# LEGO_HUB_v2_2026-03-08.net
KiCad netlist of a schematic drawn in EasyEDA Pro
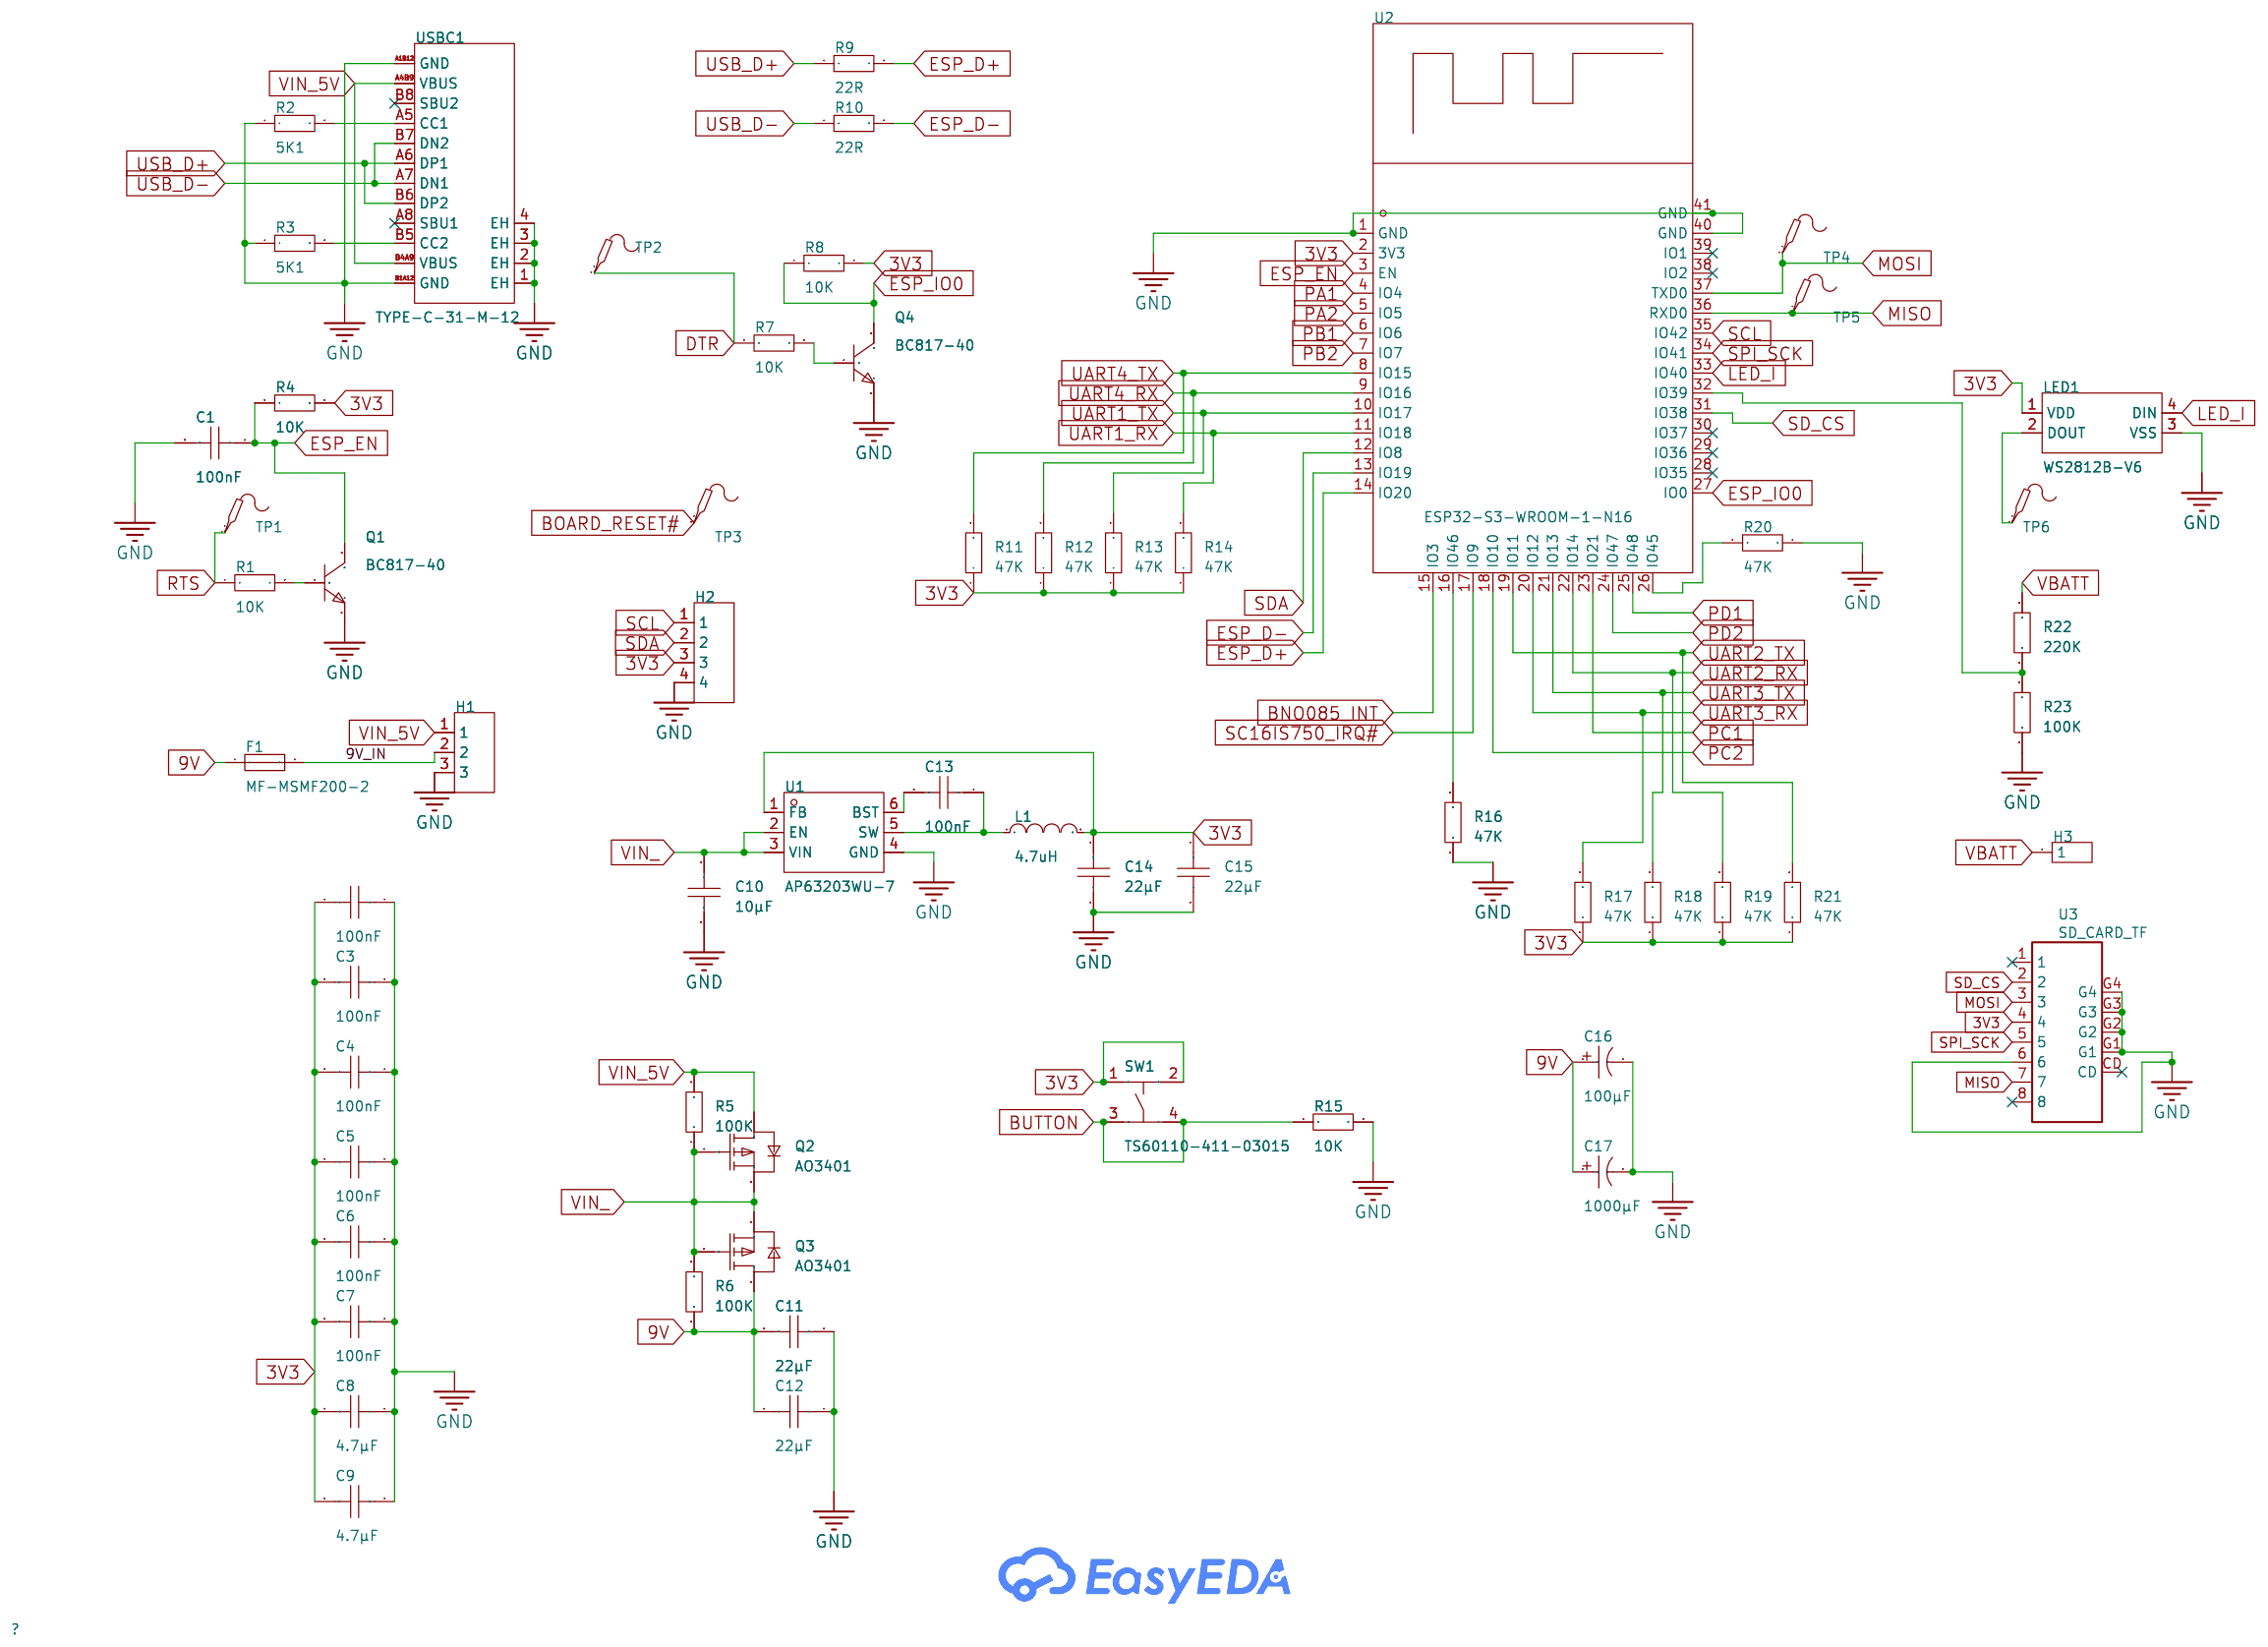
[diagram p0: P1]
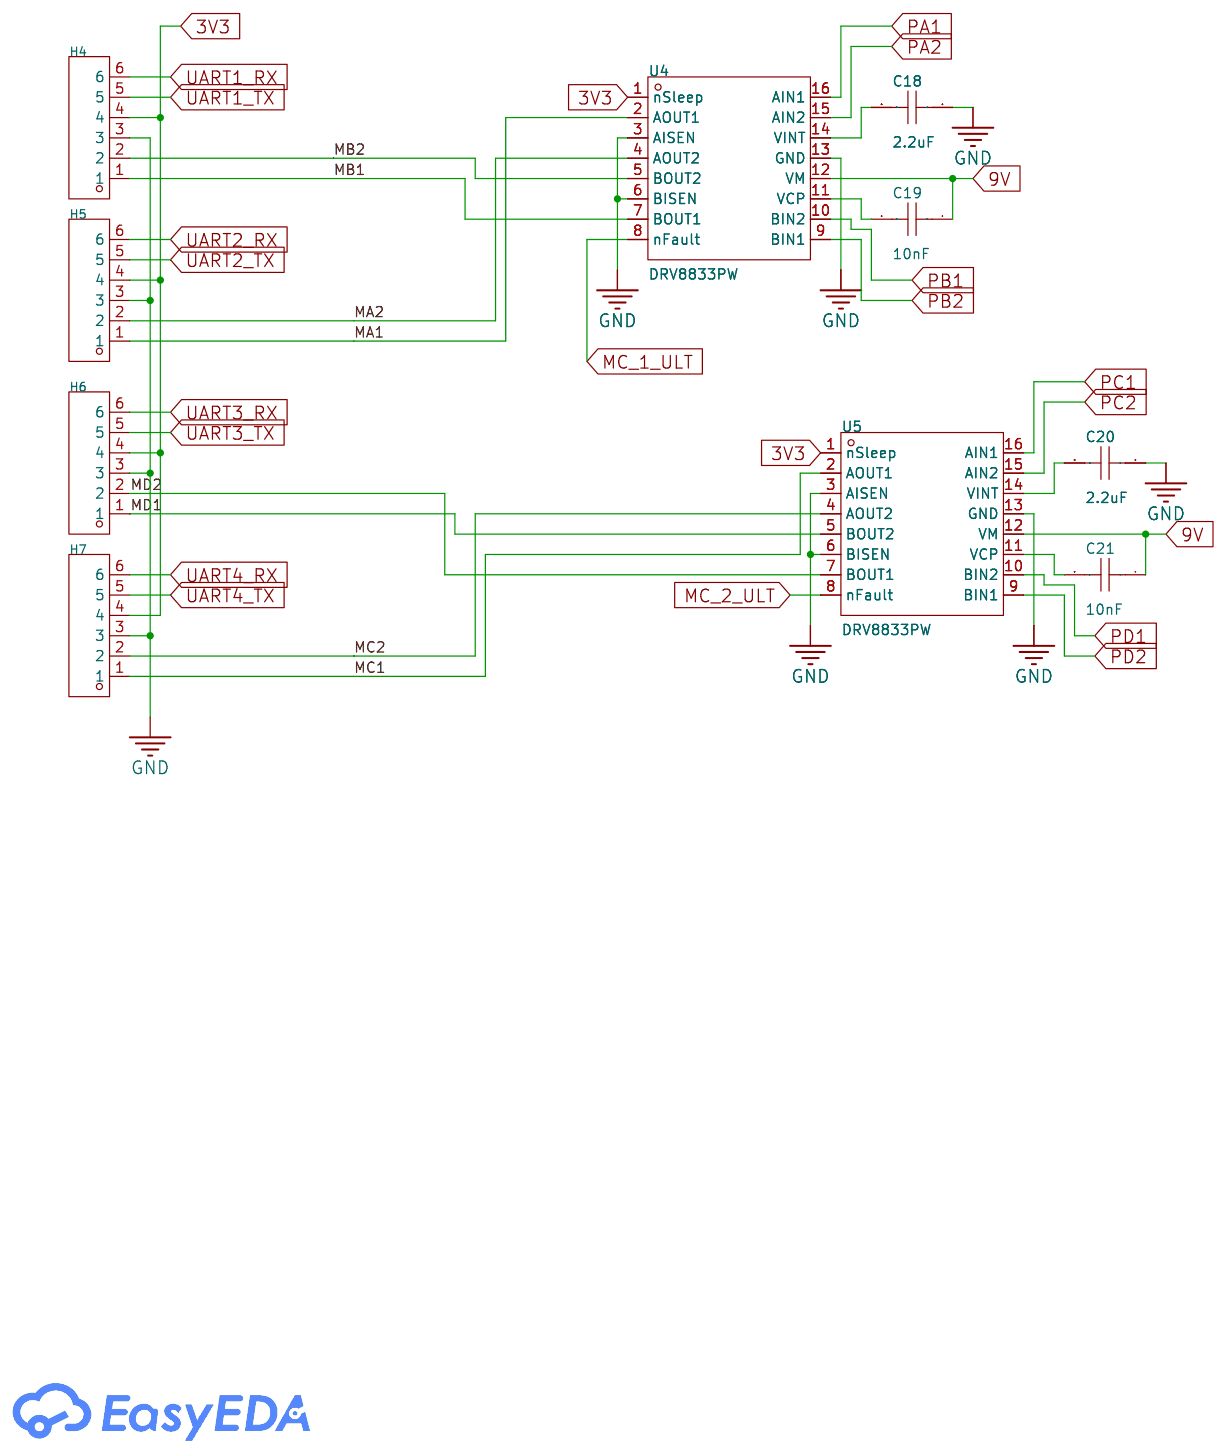
[diagram p1: P2]
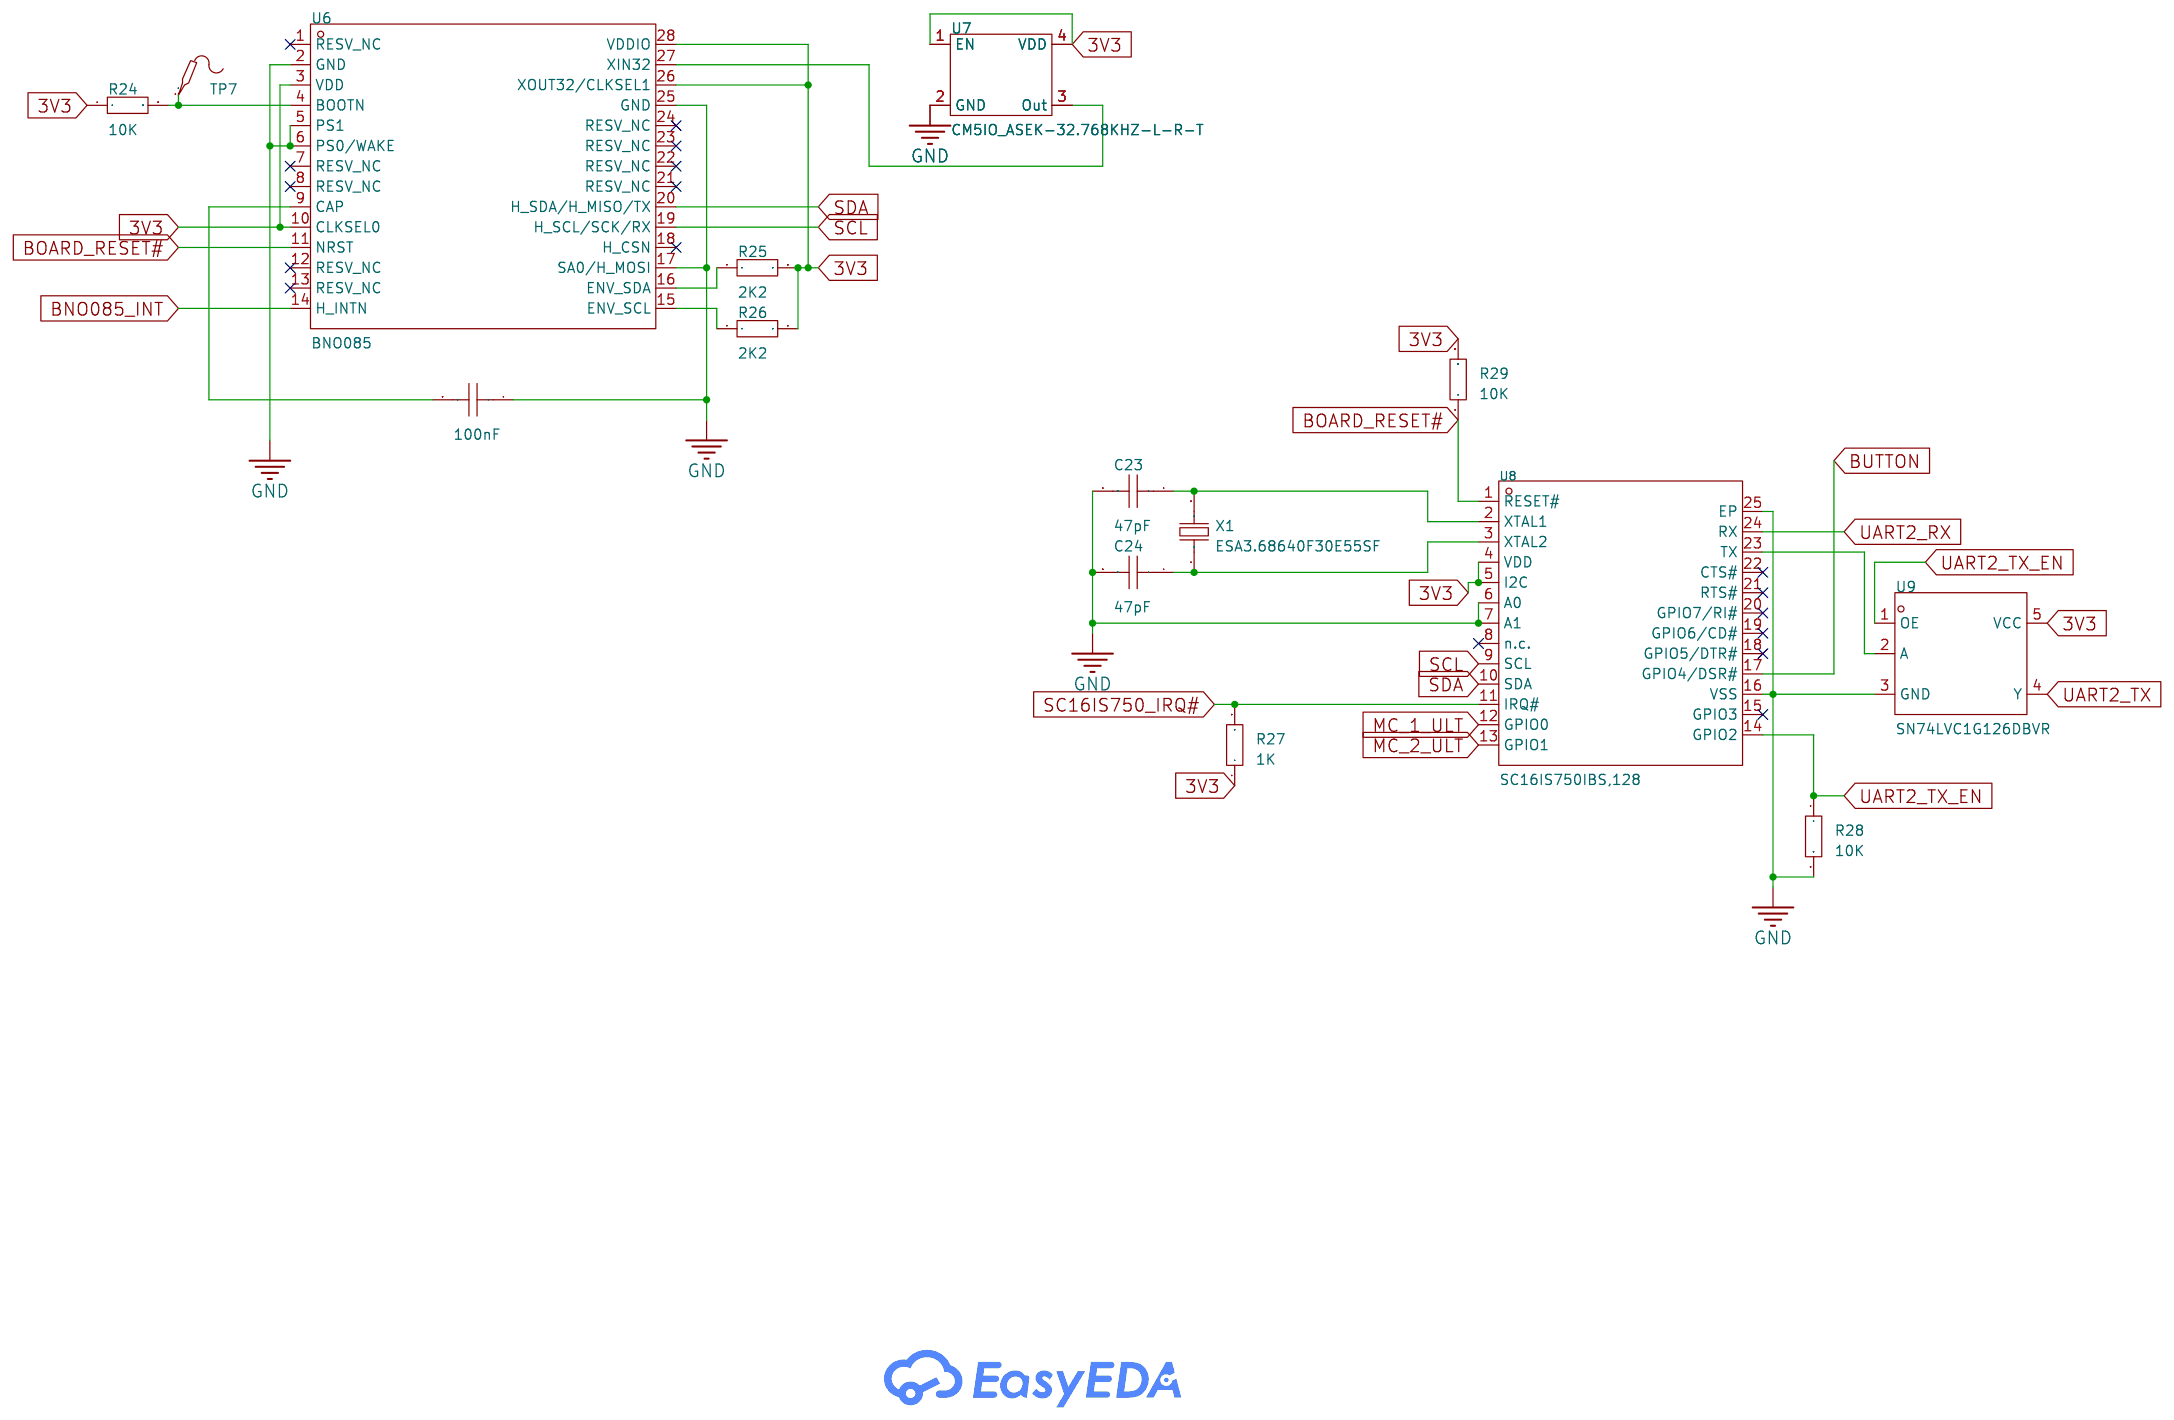
[diagram p2: P3]

(export (version "E")
  (design (tool "Eeschema 10.0.6"))
  (components
    (comp (ref "C1")
      (value "100nF")
      (footprint "easyedapro:C0603")
      (libsource (lib "easyedapro") (part "CAP"))
    )
    (comp (ref "C2")
      (value "100nF")
      (footprint "easyedapro:C0603")
      (libsource (lib "easyedapro") (part "CAP"))
    )
    (comp (ref "C3")
      (value "100nF")
      (footprint "easyedapro:C0603")
      (libsource (lib "easyedapro") (part "CAP"))
    )
    (comp (ref "C4")
      (value "100nF")
      (footprint "easyedapro:C0603")
      (libsource (lib "easyedapro") (part "CAP"))
    )
    (comp (ref "C5")
      (value "100nF")
      (footprint "easyedapro:C0603")
      (libsource (lib "easyedapro") (part "CAP"))
    )
    (comp (ref "C6")
      (value "100nF")
      (footprint "easyedapro:C0603")
      (libsource (lib "easyedapro") (part "CAP"))
    )
    (comp (ref "C7")
      (value "100nF")
      (footprint "easyedapro:C0603")
      (libsource (lib "easyedapro") (part "CAP"))
    )
    (comp (ref "C8")
      (value "4.7μF")
      (footprint "easyedapro:C0603")
      (libsource (lib "easyedapro") (part "CAP"))
    )
    (comp (ref "C9")
      (value "4.7μF")
      (footprint "easyedapro:C0603")
      (libsource (lib "easyedapro") (part "CAP"))
    )
    (comp (ref "C10")
      (value "10μF")
      (footprint "easyedapro:C0603")
      (libsource (lib "easyedapro") (part "CAP"))
    )
    (comp (ref "C11")
      (value "22μF")
      (footprint "easyedapro:C0603")
      (libsource (lib "easyedapro") (part "CAP"))
    )
    (comp (ref "C12")
      (value "22μF")
      (footprint "easyedapro:C0603")
      (libsource (lib "easyedapro") (part "CAP"))
    )
    (comp (ref "C13")
      (value "100nF")
      (footprint "easyedapro:C0603")
      (libsource (lib "easyedapro") (part "CAP"))
    )
    (comp (ref "C14")
      (value "22μF")
      (footprint "easyedapro:C0603")
      (libsource (lib "easyedapro") (part "CAP"))
    )
    (comp (ref "C15")
      (value "22μF")
      (footprint "easyedapro:C0603")
      (libsource (lib "easyedapro") (part "CAP"))
    )
    (comp (ref "C16")
      (value "100μF")
      (footprint "easyedapro:CAP-TH_BD6.3-P2.50-D1.0-FD")
      (fields (field (name "Manufacturer Part") "ERS1HM470E110T") (field (name "Manufacturer") "AISHI(艾华集团)"))
      (libsource (lib "easyedapro") (part "ERS1HM470E110T"))
    )
    (comp (ref "C17")
      (value "1000μF")
      (footprint "easyedapro:CAP-TH_BD10.0-P5.00-D1.0-FD")
      (fields (field (name "Manufacturer Part") "EGD2WM100G16OT") (field (name "Manufacturer") "AISHI(艾华集团)"))
      (libsource (lib "easyedapro") (part "EGD2WM100G16OT"))
    )
    (comp (ref "F1")
      (value "MF-MSMF200-2")
      (footprint "easyedapro:F1812")
      (fields (field (name "Manufacturer") "BOURNS"))
      (libsource (lib "easyedapro") (part "MF-MSMF200-2"))
    )
    (comp (ref "H1")
      (value "~")
      (footprint "easyedapro:HDR-TH_3P-P2.54-V-F")
      (libsource (lib "easyedapro") (part "PM254V-11-03-H85"))
    )
    (comp (ref "H2")
      (value "~")
      (footprint "easyedapro:HDR-TH_4P-P2.54-V-M")
      (libsource (lib "easyedapro") (part "PZ254V-11-04P"))
    )
    (comp (ref "H3")
      (value "~")
      (footprint "easyedapro:HDR-TH_1P-V-M_XKB_X4611WV-01I-C28D40")
      (libsource (lib "easyedapro") (part "HDR_1x1"))
    )
    (comp (ref "L1")
      (value "4.7uH")
      (footprint "easyedapro:IND-SMD_L5.8-W5.2")
      (fields (field (name "Manufacturer Part") "PCD0504MT4R7") (field (name "Manufacturer") "Viking(光颉)"))
      (libsource (lib "easyedapro") (part "PCD0504MT4R7"))
    )
    (comp (ref "LED1")
      (value "WS2812B-V6")
      (footprint "easyedapro:LED-SMD_4P-L5.0-W5.0-TL-A")
      (fields (field (name "Manufacturer") "worldsemi"))
      (libsource (lib "easyedapro") (part "WS2812B-V6"))
    )
    (comp (ref "Q1")
      (value "BC817-40")
      (footprint "easyedapro:SOT-23-3_L2.9-W1.3-P1.90-LS2.4-BR")
      (fields (field (name "Manufacturer") "ElecSuper(静芯)"))
      (libsource (lib "easyedapro") (part "BC817-40_C5249694"))
    )
    (comp (ref "Q2")
      (value "AO3401")
      (footprint "easyedapro:SOT-23-3_L2.9-W1.3-P1.90-LS2.4-BR")
      (fields (field (name "Manufacturer") "YONGYUTAI(永裕泰)"))
      (libsource (lib "easyedapro") (part "AO3401_C6575062"))
    )
    (comp (ref "Q3")
      (value "AO3401")
      (footprint "easyedapro:SOT-23-3_L2.9-W1.3-P1.90-LS2.4-BR")
      (fields (field (name "Manufacturer") "YONGYUTAI(永裕泰)"))
      (libsource (lib "easyedapro") (part "AO3401_C6575062"))
    )
    (comp (ref "Q4")
      (value "BC817-40")
      (footprint "easyedapro:SOT-23-3_L2.9-W1.3-P1.90-LS2.4-BR")
      (fields (field (name "Manufacturer") "ElecSuper(静芯)"))
      (libsource (lib "easyedapro") (part "BC817-40_C5249694"))
    )
    (comp (ref "R1") (value "10K") (footprint "easyedapro:R0201") (libsource (lib "easyedapro") (part "Res")))
    (comp (ref "R2") (value "5K1") (footprint "easyedapro:R0201") (libsource (lib "easyedapro") (part "Res")))
    (comp (ref "R3") (value "5K1") (footprint "easyedapro:R0201") (libsource (lib "easyedapro") (part "Res")))
    (comp (ref "R4") (value "10K") (footprint "easyedapro:R0201") (libsource (lib "easyedapro") (part "Res")))
    (comp (ref "R5")
      (value "100K")
      (footprint "easyedapro:R0201")
      (libsource (lib "easyedapro") (part "Res"))
    )
    (comp (ref "R6")
      (value "100K")
      (footprint "easyedapro:R0201")
      (libsource (lib "easyedapro") (part "Res"))
    )
    (comp (ref "R7") (value "10K") (footprint "easyedapro:R0201") (libsource (lib "easyedapro") (part "Res")))
    (comp (ref "R8") (value "10K") (footprint "easyedapro:R0201") (libsource (lib "easyedapro") (part "Res")))
    (comp (ref "R9") (value "22R") (footprint "easyedapro:R0201") (libsource (lib "easyedapro") (part "Res")))
    (comp (ref "R10")
      (value "22R")
      (footprint "easyedapro:R0201")
      (libsource (lib "easyedapro") (part "Res"))
    )
    (comp (ref "R11")
      (value "47K")
      (footprint "easyedapro:R0201")
      (libsource (lib "easyedapro") (part "Res"))
    )
    (comp (ref "R12")
      (value "47K")
      (footprint "easyedapro:R0201")
      (libsource (lib "easyedapro") (part "Res"))
    )
    (comp (ref "R13")
      (value "47K")
      (footprint "easyedapro:R0201")
      (libsource (lib "easyedapro") (part "Res"))
    )
    (comp (ref "R14")
      (value "47K")
      (footprint "easyedapro:R0201")
      (libsource (lib "easyedapro") (part "Res"))
    )
    (comp (ref "R15")
      (value "10K")
      (footprint "easyedapro:R0201")
      (libsource (lib "easyedapro") (part "Res"))
    )
    (comp (ref "R16")
      (value "47K")
      (footprint "easyedapro:R0201")
      (libsource (lib "easyedapro") (part "Res"))
    )
    (comp (ref "R17")
      (value "47K")
      (footprint "easyedapro:R0201")
      (libsource (lib "easyedapro") (part "Res"))
    )
    (comp (ref "R18")
      (value "47K")
      (footprint "easyedapro:R0201")
      (libsource (lib "easyedapro") (part "Res"))
    )
    (comp (ref "R19")
      (value "47K")
      (footprint "easyedapro:R0201")
      (libsource (lib "easyedapro") (part "Res"))
    )
    (comp (ref "R20")
      (value "47K")
      (footprint "easyedapro:R0201")
      (libsource (lib "easyedapro") (part "Res"))
    )
    (comp (ref "R21")
      (value "47K")
      (footprint "easyedapro:R0201")
      (libsource (lib "easyedapro") (part "Res"))
    )
    (comp (ref "R22")
      (value "220K")
      (footprint "easyedapro:R0201")
      (libsource (lib "easyedapro") (part "Res"))
    )
    (comp (ref "R23")
      (value "100K")
      (footprint "easyedapro:R0201")
      (libsource (lib "easyedapro") (part "Res"))
    )
    (comp (ref "SW1")
      (value "TS60110-411-03015")
      (footprint "easyedapro:SW-SMD_4P-L5.2-W5.2-P3.70-LS6.4-BL")
      (fields (field (name "Manufacturer") "HMTCONN(华明通)"))
      (libsource (lib "easyedapro") (part "TS60110-411-03015"))
    )
    (comp (ref "TP1")
      (value "~")
      (footprint "easyedapro:Test-Point-0.5mm")
      (description "Test Point 测试点")
      (libsource (lib "easyedapro") (part "Test-Point"))
    )
    (comp (ref "TP2")
      (value "~")
      (footprint "easyedapro:Test-Point-0.5mm")
      (description "Test Point 测试点")
      (libsource (lib "easyedapro") (part "Test-Point"))
    )
    (comp (ref "TP3")
      (value "~")
      (footprint "easyedapro:Test-Point-0.5mm")
      (description "Test Point 测试点")
      (libsource (lib "easyedapro") (part "Test-Point"))
    )
    (comp (ref "TP4")
      (value "~")
      (footprint "easyedapro:Test-Point-0.5mm")
      (description "Test Point 测试点")
      (libsource (lib "easyedapro") (part "Test-Point"))
    )
    (comp (ref "TP5")
      (value "~")
      (footprint "easyedapro:Test-Point-0.5mm")
      (description "Test Point 测试点")
      (libsource (lib "easyedapro") (part "Test-Point"))
    )
    (comp (ref "TP6")
      (value "~")
      (footprint "easyedapro:Test-Point-0.5mm")
      (description "Test Point 测试点")
      (libsource (lib "easyedapro") (part "Test-Point"))
    )
    (comp (ref "U1")
      (value "AP63203WU-7")
      (footprint "easyedapro:TSOT-26_L2.9-W1.6-P0.95-LS2.8-BL")
      (fields (field (name "Manufacturer") "DIODES(美台)"))
      (libsource (lib "easyedapro") (part "AP63203WU-7"))
    )
    (comp (ref "U2")
      (value "ESP32-S3-WROOM-1-N16")
      (footprint "easyedapro:WIRELM-SMD_ESP32-S3-WROOM-1")
      (fields (field (name "Manufacturer") "ESPRESSIF(乐鑫)"))
      (libsource (lib "easyedapro") (part "ESP32-S3-WROOM-1(N16)"))
    )
    (comp (ref "U3")
      (value "SD_CARD_TF")
      (footprint "easyedapro:MICRO-USB-SMD_MICRO-SD")
      (fields (field (name "Manufacturer Part") "SD_Card_TF") (field (name "Contributor") "lcsc"))
      (libsource (lib "easyedapro") (part "SD_CARD_TF"))
    )
    (comp (ref "USBC1")
      (value "TYPE-C-31-M-12")
      (footprint "easyedapro:USB-C_SMD-TYPE-C-31-M-12_1")
      (fields (field (name "Manufacturer") "韩国韩荣"))
      (libsource (lib "easyedapro") (part "TYPE-C-31-M-12"))
    )
    (comp (ref "C18")
      (value "2.2uF")
      (footprint "easyedapro:C0603")
      (libsource (lib "easyedapro") (part "CAP"))
    )
    (comp (ref "C19")
      (value "10nF")
      (footprint "easyedapro:C0603")
      (libsource (lib "easyedapro") (part "CAP"))
    )
    (comp (ref "C20")
      (value "2.2uF")
      (footprint "easyedapro:C0603")
      (libsource (lib "easyedapro") (part "CAP"))
    )
    (comp (ref "C21")
      (value "10nF")
      (footprint "easyedapro:C0603")
      (libsource (lib "easyedapro") (part "CAP"))
    )
    (comp (ref "H4")
      (value "~")
      (footprint "easyedapro:HDR-TH_6P-P2.54-V-F")
      (libsource (lib "easyedapro") (part "Header-Female-2.54_1x6"))
    )
    (comp (ref "H5")
      (value "~")
      (footprint "easyedapro:HDR-TH_6P-P2.54-V-F")
      (libsource (lib "easyedapro") (part "Header-Female-2.54_1x6"))
    )
    (comp (ref "H6")
      (value "~")
      (footprint "easyedapro:HDR-TH_6P-P2.54-V-F")
      (libsource (lib "easyedapro") (part "Header-Female-2.54_1x6"))
    )
    (comp (ref "H7")
      (value "~")
      (footprint "easyedapro:HDR-TH_6P-P2.54-V-F")
      (libsource (lib "easyedapro") (part "Header-Female-2.54_1x6"))
    )
    (comp (ref "U4")
      (value "DRV8833PW")
      (footprint "easyedapro:TSSOP-16_L5.0-W4.4-P0.65-LS6.4-BL")
      (fields (field (name "Manufacturer") "TI(德州仪器)"))
      (libsource (lib "easyedapro") (part "DRV8833PW_C3681295"))
    )
    (comp (ref "U5")
      (value "DRV8833PW")
      (footprint "easyedapro:TSSOP-16_L5.0-W4.4-P0.65-LS6.4-BL")
      (fields (field (name "Manufacturer") "TI(德州仪器)"))
      (libsource (lib "easyedapro") (part "DRV8833PW_C3681295"))
    )
    (comp (ref "C22")
      (value "100nF")
      (footprint "easyedapro:C0603")
      (libsource (lib "easyedapro") (part "CAP"))
    )
    (comp (ref "C23")
      (value "47pF")
      (footprint "easyedapro:C0603")
      (libsource (lib "easyedapro") (part "CAP"))
    )
    (comp (ref "C24")
      (value "47pF")
      (footprint "easyedapro:C0603")
      (libsource (lib "easyedapro") (part "CAP"))
    )
    (comp (ref "R24")
      (value "10K")
      (footprint "easyedapro:R0201")
      (libsource (lib "easyedapro") (part "Res"))
    )
    (comp (ref "R25")
      (value "2K2")
      (footprint "easyedapro:R0201")
      (libsource (lib "easyedapro") (part "Res"))
    )
    (comp (ref "R26")
      (value "2K2")
      (footprint "easyedapro:R0201")
      (libsource (lib "easyedapro") (part "Res"))
    )
    (comp (ref "R27") (value "1K") (footprint "easyedapro:R0201") (libsource (lib "easyedapro") (part "Res")))
    (comp (ref "R28")
      (value "10K")
      (footprint "easyedapro:R0201")
      (libsource (lib "easyedapro") (part "Res"))
    )
    (comp (ref "R29")
      (value "10K")
      (footprint "easyedapro:R0201")
      (libsource (lib "easyedapro") (part "Res"))
    )
    (comp (ref "TP7")
      (value "~")
      (footprint "easyedapro:Test-Point-0.5mm")
      (description "Test Point 测试点")
      (libsource (lib "easyedapro") (part "Test-Point"))
    )
    (comp (ref "U6")
      (value "BNO085")
      (footprint "easyedapro:LGA-28_L5.2-W3.8-P0.50-BL")
      (fields (field (name "Manufacturer") "CEVA"))
      (libsource (lib "easyedapro") (part "BNO085_C5189642"))
    )
    (comp (ref "U7")
      (value "ASEK-32.768KHZ-L-R-T")
      (footprint "easyedapro:Crystal:Crystal_SMD_3225-4Pin_3.2x2.5mm")
      (libsource (lib "easyedapro") (part "CM5IO_ASEK-32.768KHZ-L-R-T"))
    )
    (comp (ref "U8")
      (value "SC16IS750IBS,128")
      (footprint "easyedapro:HVQFN-24_L4.0-W4.0-P0.50-BL-EP2.6")
      (fields (field (name "Manufacturer") "NXP(恩智浦)"))
      (libsource (lib "easyedapro") (part "SC16IS750IBS,128"))
    )
    (comp (ref "U9")
      (value "SN74LVC1G126DBVR")
      (footprint "easyedapro:SOT-23-5_L3.0-W1.7-P0.95-LS2.8-BR")
      (fields (field (name "Manufacturer") "TI"))
      (libsource (lib "easyedapro") (part "SN74LVC1G126DBVR"))
    )
    (comp (ref "X1")
      (value "ESA3.68640F30E55SF")
      (footprint "easyedapro:CRYSTAL-SMD_L11.4-W4.7-LS12.7")
      (libsource (lib "easyedapro") (part "ESA3.68640F30E55SF"))
    )
  )
  (nets
    (net (code "1") (name "3V3") (class "Default")
      (node (ref "C14") (pin "1") (pinfunction "1_1") (pintype "input"))
      (node (ref "C15") (pin "1") (pinfunction "1_1") (pintype "input"))
      (node (ref "C2") (pin "2") (pinfunction "2_2") (pintype "input"))
      (node (ref "C3") (pin "2") (pinfunction "2_2") (pintype "input"))
      (node (ref "C4") (pin "2") (pinfunction "2_2") (pintype "input"))
      (node (ref "C5") (pin "2") (pinfunction "2_2") (pintype "input"))
      (node (ref "C6") (pin "2") (pinfunction "2_2") (pintype "input"))
      (node (ref "C7") (pin "2") (pinfunction "2_2") (pintype "input"))
      (node (ref "C8") (pin "2") (pinfunction "2_2") (pintype "input"))
      (node (ref "C9") (pin "2") (pinfunction "2_2") (pintype "input"))
      (node (ref "H2") (pin "3") (pinfunction "3_3") (pintype "unspecified"))
      (node (ref "H4") (pin "4") (pinfunction "4_4") (pintype "input"))
      (node (ref "H5") (pin "4") (pinfunction "4_4") (pintype "input"))
      (node (ref "H6") (pin "4") (pinfunction "4_4") (pintype "input"))
      (node (ref "H7") (pin "4") (pinfunction "4_4") (pintype "input"))
      (node (ref "L1") (pin "2") (pinfunction "2_2") (pintype "unspecified"))
      (node (ref "LED1") (pin "1") (pinfunction "VDD_1") (pintype "unspecified"))
      (node (ref "R11") (pin "1") (pinfunction "1_1") (pintype "input"))
      (node (ref "R12") (pin "1") (pinfunction "1_1") (pintype "input"))
      (node (ref "R13") (pin "1") (pinfunction "1_1") (pintype "input"))
      (node (ref "R14") (pin "1") (pinfunction "1_1") (pintype "input"))
      (node (ref "R17") (pin "1") (pinfunction "1_1") (pintype "input"))
      (node (ref "R18") (pin "1") (pinfunction "1_1") (pintype "input"))
      (node (ref "R19") (pin "1") (pinfunction "1_1") (pintype "input"))
      (node (ref "R21") (pin "1") (pinfunction "1_1") (pintype "input"))
      (node (ref "R24") (pin "1") (pinfunction "1_1") (pintype "input"))
      (node (ref "R25") (pin "2") (pinfunction "2_2") (pintype "input"))
      (node (ref "R26") (pin "2") (pinfunction "2_2") (pintype "input"))
      (node (ref "R27") (pin "1") (pinfunction "1_1") (pintype "input"))
      (node (ref "R29") (pin "2") (pinfunction "2_2") (pintype "input"))
      (node (ref "R4") (pin "2") (pinfunction "2_2") (pintype "input"))
      (node (ref "R8") (pin "2") (pinfunction "2_2") (pintype "input"))
      (node (ref "SW1") (pin "1") (pinfunction "1_1") (pintype "unspecified"))
      (node (ref "SW1") (pin "2") (pinfunction "2_2") (pintype "unspecified"))
      (node (ref "U1") (pin "1") (pinfunction "FB_1") (pintype "unspecified"))
      (node (ref "U2") (pin "2") (pinfunction "3V3_2") (pintype "unspecified"))
      (node (ref "U3") (pin "4") (pinfunction "4_4") (pintype "unspecified"))
      (node (ref "U4") (pin "1") (pinfunction "nSleep_1") (pintype "unspecified"))
      (node (ref "U5") (pin "1") (pinfunction "nSleep_1") (pintype "unspecified"))
      (node (ref "U6") (pin "10") (pinfunction "CLKSEL0_10") (pintype "unspecified"))
      (node (ref "U6") (pin "26") (pinfunction "XOUT32/CLKSEL1_26") (pintype "unspecified"))
      (node (ref "U6") (pin "28") (pinfunction "VDDIO_28") (pintype "unspecified"))
      (node (ref "U6") (pin "3") (pinfunction "VDD_3") (pintype "unspecified"))
      (node (ref "U7") (pin "1") (pinfunction "EN_1") (pintype "input"))
      (node (ref "U7") (pin "4") (pinfunction "VDD_4") (pintype "unspecified"))
      (node (ref "U8") (pin "4") (pinfunction "VDD_4") (pintype "input"))
      (node (ref "U8") (pin "5") (pinfunction "I2C_5") (pintype "input"))
      (node (ref "U9") (pin "5") (pinfunction "VCC_5") (pintype "unspecified"))
    )
    (net (code "2") (name "9V") (class "Default")
      (node (ref "C11") (pin "2") (pinfunction "2_2") (pintype "input"))
      (node (ref "C12") (pin "2") (pinfunction "2_2") (pintype "input"))
      (node (ref "C16") (pin "1") (pinfunction "1_1") (pintype "input"))
      (node (ref "C17") (pin "1") (pinfunction "1_1") (pintype "input"))
      (node (ref "C19") (pin "1") (pinfunction "1_1") (pintype "input"))
      (node (ref "C21") (pin "1") (pinfunction "1_1") (pintype "input"))
      (node (ref "F1") (pin "1") (pinfunction "1_1") (pintype "unspecified"))
      (node (ref "Q3") (pin "3") (pinfunction "D_3") (pintype "unspecified"))
      (node (ref "R6") (pin "1") (pinfunction "1_1") (pintype "input"))
      (node (ref "U4") (pin "12") (pinfunction "VM_12") (pintype "unspecified"))
      (node (ref "U5") (pin "12") (pinfunction "VM_12") (pintype "unspecified"))
    )
    (net (code "3") (name "9V_IN") (class "Default")
      (node (ref "F1") (pin "2") (pinfunction "2_2") (pintype "unspecified"))
      (node (ref "H1") (pin "2") (pinfunction "2_2") (pintype "unspecified"))
    )
    (net (code "4") (name "BNO085_INT") (class "Default")
      (node (ref "U2") (pin "15") (pinfunction "IO3_15") (pintype "unspecified"))
      (node (ref "U6") (pin "14") (pinfunction "H_INTN_14") (pintype "unspecified"))
    )
    (net (code "5") (name "BOARD_RESET#") (class "Default")
      (node (ref "R29") (pin "1") (pinfunction "1_1") (pintype "input"))
      (node (ref "TP3") (pin "1") (pinfunction "1_1") (pintype "unspecified"))
      (node (ref "U6") (pin "11") (pinfunction "NRST_11") (pintype "unspecified"))
      (node (ref "U8") (pin "1") (pinfunction "RESET#_1") (pintype "input"))
    )
    (net (code "6") (name "BUTTON") (class "Default")
      (node (ref "R15") (pin "1") (pinfunction "1_1") (pintype "input"))
      (node (ref "SW1") (pin "3") (pinfunction "3_3") (pintype "unspecified"))
      (node (ref "SW1") (pin "4") (pinfunction "4_4") (pintype "unspecified"))
      (node (ref "U8") (pin "17") (pinfunction "GPIO4/DSR#_17") (pintype "input"))
    )
    (net (code "7") (name "DTR") (class "Default")
      (node (ref "R7") (pin "1") (pinfunction "1_1") (pintype "input"))
      (node (ref "TP2") (pin "1") (pinfunction "1_1") (pintype "unspecified"))
    )
    (net (code "8") (name "ESP_D+") (class "Default")
      (node (ref "R9") (pin "2") (pinfunction "2_2") (pintype "input"))
      (node (ref "U2") (pin "14") (pinfunction "IO20_14") (pintype "unspecified"))
    )
    (net (code "9") (name "ESP_D-") (class "Default")
      (node (ref "R10") (pin "2") (pinfunction "2_2") (pintype "input"))
      (node (ref "U2") (pin "13") (pinfunction "IO19_13") (pintype "unspecified"))
    )
    (net (code "10") (name "ESP_EN") (class "Default")
      (node (ref "C1") (pin "1") (pinfunction "1_1") (pintype "input"))
      (node (ref "Q1") (pin "3") (pinfunction "C_3") (pintype "input"))
      (node (ref "R4") (pin "1") (pinfunction "1_1") (pintype "input"))
      (node (ref "U2") (pin "3") (pinfunction "EN_3") (pintype "unspecified"))
    )
    (net (code "11") (name "ESP_IO0") (class "Default")
      (node (ref "Q4") (pin "3") (pinfunction "C_3") (pintype "input"))
      (node (ref "R8") (pin "1") (pinfunction "1_1") (pintype "input"))
      (node (ref "U2") (pin "27") (pinfunction "IO0_27") (pintype "unspecified"))
    )
    (net (code "12") (name "GND") (class "Default")
      (node (ref "C1") (pin "2") (pinfunction "2_2") (pintype "input"))
      (node (ref "C10") (pin "2") (pinfunction "2_2") (pintype "input"))
      (node (ref "C11") (pin "1") (pinfunction "1_1") (pintype "input"))
      (node (ref "C12") (pin "1") (pinfunction "1_1") (pintype "input"))
      (node (ref "C14") (pin "2") (pinfunction "2_2") (pintype "input"))
      (node (ref "C15") (pin "2") (pinfunction "2_2") (pintype "input"))
      (node (ref "C16") (pin "2") (pinfunction "2_2") (pintype "input"))
      (node (ref "C17") (pin "2") (pinfunction "2_2") (pintype "input"))
      (node (ref "C18") (pin "1") (pinfunction "1_1") (pintype "input"))
      (node (ref "C2") (pin "1") (pinfunction "1_1") (pintype "input"))
      (node (ref "C20") (pin "1") (pinfunction "1_1") (pintype "input"))
      (node (ref "C22") (pin "1") (pinfunction "1_1") (pintype "input"))
      (node (ref "C23") (pin "2") (pinfunction "2_2") (pintype "input"))
      (node (ref "C24") (pin "2") (pinfunction "2_2") (pintype "input"))
      (node (ref "C3") (pin "1") (pinfunction "1_1") (pintype "input"))
      (node (ref "C4") (pin "1") (pinfunction "1_1") (pintype "input"))
      (node (ref "C5") (pin "1") (pinfunction "1_1") (pintype "input"))
      (node (ref "C6") (pin "1") (pinfunction "1_1") (pintype "input"))
      (node (ref "C7") (pin "1") (pinfunction "1_1") (pintype "input"))
      (node (ref "C8") (pin "1") (pinfunction "1_1") (pintype "input"))
      (node (ref "C9") (pin "1") (pinfunction "1_1") (pintype "input"))
      (node (ref "H1") (pin "3") (pinfunction "3_3") (pintype "unspecified"))
      (node (ref "H2") (pin "4") (pinfunction "4_4") (pintype "unspecified"))
      (node (ref "H4") (pin "3") (pinfunction "3_3") (pintype "input"))
      (node (ref "H5") (pin "3") (pinfunction "3_3") (pintype "input"))
      (node (ref "H6") (pin "3") (pinfunction "3_3") (pintype "input"))
      (node (ref "H7") (pin "3") (pinfunction "3_3") (pintype "input"))
      (node (ref "LED1") (pin "3") (pinfunction "VSS_3") (pintype "unspecified"))
      (node (ref "Q1") (pin "2") (pinfunction "E_2") (pintype "input"))
      (node (ref "Q4") (pin "2") (pinfunction "E_2") (pintype "input"))
      (node (ref "R15") (pin "2") (pinfunction "2_2") (pintype "input"))
      (node (ref "R16") (pin "1") (pinfunction "1_1") (pintype "input"))
      (node (ref "R2") (pin "1") (pinfunction "1_1") (pintype "input"))
      (node (ref "R20") (pin "1") (pinfunction "1_1") (pintype "input"))
      (node (ref "R23") (pin "1") (pinfunction "1_1") (pintype "input"))
      (node (ref "R28") (pin "2") (pinfunction "2_2") (pintype "input"))
      (node (ref "R3") (pin "1") (pinfunction "1_1") (pintype "input"))
      (node (ref "U1") (pin "4") (pinfunction "GND_4") (pintype "unspecified"))
      (node (ref "U2") (pin "1") (pinfunction "GND_1") (pintype "unspecified"))
      (node (ref "U2") (pin "40") (pinfunction "GND_40") (pintype "unspecified"))
      (node (ref "U2") (pin "41") (pinfunction "GND_41") (pintype "unspecified"))
      (node (ref "U3") (pin "6") (pinfunction "6_6") (pintype "unspecified"))
      (node (ref "U3") (pin "G1") (pinfunction "G1_G1") (pintype "unspecified"))
      (node (ref "U3") (pin "G2") (pinfunction "G2_G2") (pintype "unspecified"))
      (node (ref "U3") (pin "G3") (pinfunction "G3_G3") (pintype "unspecified"))
      (node (ref "U3") (pin "G4") (pinfunction "G4_G4") (pintype "unspecified"))
      (node (ref "U4") (pin "13") (pinfunction "GND_13") (pintype "unspecified"))
      (node (ref "U4") (pin "3") (pinfunction "AISEN_3") (pintype "unspecified"))
      (node (ref "U4") (pin "6") (pinfunction "BISEN_6") (pintype "unspecified"))
      (node (ref "U5") (pin "13") (pinfunction "GND_13") (pintype "unspecified"))
      (node (ref "U5") (pin "3") (pinfunction "AISEN_3") (pintype "unspecified"))
      (node (ref "U5") (pin "6") (pinfunction "BISEN_6") (pintype "unspecified"))
      (node (ref "U6") (pin "17") (pinfunction "SA0/H_MOSI_17") (pintype "unspecified"))
      (node (ref "U6") (pin "2") (pinfunction "GND_2") (pintype "unspecified"))
      (node (ref "U6") (pin "25") (pinfunction "GND_25") (pintype "unspecified"))
      (node (ref "U6") (pin "5") (pinfunction "PS1_5") (pintype "unspecified"))
      (node (ref "U6") (pin "6") (pinfunction "PS0/WAKE_6") (pintype "unspecified"))
      (node (ref "U7") (pin "2") (pinfunction "GND_2") (pintype "unspecified"))
      (node (ref "U8") (pin "16") (pinfunction "VSS_16") (pintype "input"))
      (node (ref "U8") (pin "25") (pinfunction "EP_25") (pintype "input"))
      (node (ref "U8") (pin "6") (pinfunction "A0_6") (pintype "input"))
      (node (ref "U8") (pin "7") (pinfunction "A1_7") (pintype "input"))
      (node (ref "U9") (pin "3") (pinfunction "GND_3") (pintype "unspecified"))
      (node (ref "USBC1") (pin "1") (pinfunction "EH_1") (pintype "unspecified"))
      (node (ref "USBC1") (pin "2") (pinfunction "EH_2") (pintype "unspecified"))
      (node (ref "USBC1") (pin "3") (pinfunction "EH_3") (pintype "unspecified"))
      (node (ref "USBC1") (pin "4") (pinfunction "EH_4") (pintype "unspecified"))
      (node (ref "USBC1") (pin "A1B12") (pinfunction "GND_A1B12") (pintype "unspecified"))
      (node (ref "USBC1") (pin "B1A12") (pinfunction "GND_B1A12") (pintype "unspecified"))
    )
    (net (code "13") (name "LED_I") (class "Default")
      (node (ref "LED1") (pin "4") (pinfunction "DIN_4") (pintype "unspecified"))
      (node (ref "U2") (pin "33") (pinfunction "IO40_33") (pintype "unspecified"))
    )
    (net (code "14") (name "MA1") (class "Default")
      (node (ref "H5") (pin "1") (pinfunction "1_1") (pintype "input"))
      (node (ref "U4") (pin "2") (pinfunction "AOUT1_2") (pintype "unspecified"))
    )
    (net (code "15") (name "MA2") (class "Default")
      (node (ref "H5") (pin "2") (pinfunction "2_2") (pintype "input"))
      (node (ref "U4") (pin "4") (pinfunction "AOUT2_4") (pintype "unspecified"))
    )
    (net (code "16") (name "MB1") (class "Default")
      (node (ref "H4") (pin "1") (pinfunction "1_1") (pintype "input"))
      (node (ref "U4") (pin "7") (pinfunction "BOUT1_7") (pintype "unspecified"))
    )
    (net (code "17") (name "MB2") (class "Default")
      (node (ref "H4") (pin "2") (pinfunction "2_2") (pintype "input"))
      (node (ref "U4") (pin "5") (pinfunction "BOUT2_5") (pintype "unspecified"))
    )
    (net (code "18") (name "MC1") (class "Default")
      (node (ref "H7") (pin "1") (pinfunction "1_1") (pintype "input"))
      (node (ref "U5") (pin "2") (pinfunction "AOUT1_2") (pintype "unspecified"))
    )
    (net (code "19") (name "MC2") (class "Default")
      (node (ref "H7") (pin "2") (pinfunction "2_2") (pintype "input"))
      (node (ref "U5") (pin "4") (pinfunction "AOUT2_4") (pintype "unspecified"))
    )
    (net (code "20") (name "MC_1_ULT") (class "Default")
      (node (ref "U4") (pin "8") (pinfunction "nFault_8") (pintype "unspecified"))
      (node (ref "U8") (pin "12") (pinfunction "GPIO0_12") (pintype "input"))
    )
    (net (code "21") (name "MC_2_ULT") (class "Default")
      (node (ref "U5") (pin "8") (pinfunction "nFault_8") (pintype "unspecified"))
      (node (ref "U8") (pin "13") (pinfunction "GPIO1_13") (pintype "input"))
    )
    (net (code "22") (name "MD1") (class "Default")
      (node (ref "H6") (pin "1") (pinfunction "1_1") (pintype "input"))
      (node (ref "U5") (pin "5") (pinfunction "BOUT2_5") (pintype "unspecified"))
    )
    (net (code "23") (name "MD2") (class "Default")
      (node (ref "H6") (pin "2") (pinfunction "2_2") (pintype "input"))
      (node (ref "U5") (pin "7") (pinfunction "BOUT1_7") (pintype "unspecified"))
    )
    (net (code "24") (name "MISO") (class "Default")
      (node (ref "TP5") (pin "1") (pinfunction "1_1") (pintype "unspecified"))
      (node (ref "U2") (pin "36") (pinfunction "RXD0_36") (pintype "unspecified"))
      (node (ref "U3") (pin "7") (pinfunction "7_7") (pintype "unspecified"))
    )
    (net (code "25") (name "MOSI") (class "Default")
      (node (ref "TP4") (pin "1") (pinfunction "1_1") (pintype "unspecified"))
      (node (ref "U2") (pin "37") (pinfunction "TXD0_37") (pintype "unspecified"))
      (node (ref "U3") (pin "3") (pinfunction "3_3") (pintype "unspecified"))
    )
    (net (code "26") (name "Net-(LED1-DOUT)") (class "Default")
      (node (ref "LED1") (pin "2") (pinfunction "DOUT_2") (pintype "unspecified"))
      (node (ref "TP6") (pin "1") (pinfunction "1_1") (pintype "unspecified"))
    )
    (net (code "27") (name "Net-(Q1-B)") (class "Default")
      (node (ref "Q1") (pin "1") (pinfunction "B_1") (pintype "input"))
      (node (ref "R1") (pin "2") (pinfunction "2_2") (pintype "input"))
    )
    (net (code "28") (name "Net-(Q4-B)") (class "Default")
      (node (ref "Q4") (pin "1") (pinfunction "B_1") (pintype "input"))
      (node (ref "R7") (pin "2") (pinfunction "2_2") (pintype "input"))
    )
    (net (code "29") (name "Net-(U1-BST)") (class "Default")
      (node (ref "C13") (pin "2") (pinfunction "2_2") (pintype "input"))
      (node (ref "U1") (pin "6") (pinfunction "BST_6") (pintype "unspecified"))
    )
    (net (code "30") (name "Net-(U1-SW)") (class "Default")
      (node (ref "C13") (pin "1") (pinfunction "1_1") (pintype "input"))
      (node (ref "L1") (pin "1") (pinfunction "1_1") (pintype "unspecified"))
      (node (ref "U1") (pin "5") (pinfunction "SW_5") (pintype "unspecified"))
    )
    (net (code "31") (name "Net-(U2-IO39)") (class "Default")
      (node (ref "R22") (pin "1") (pinfunction "1_1") (pintype "input"))
      (node (ref "R23") (pin "2") (pinfunction "2_2") (pintype "input"))
      (node (ref "U2") (pin "32") (pinfunction "IO39_32") (pintype "unspecified"))
    )
    (net (code "32") (name "Net-(U2-IO45)") (class "Default")
      (node (ref "R20") (pin "2") (pinfunction "2_2") (pintype "input"))
      (node (ref "U2") (pin "26") (pinfunction "IO45_26") (pintype "unspecified"))
    )
    (net (code "33") (name "Net-(U2-IO46)") (class "Default")
      (node (ref "R16") (pin "2") (pinfunction "2_2") (pintype "input"))
      (node (ref "U2") (pin "16") (pinfunction "IO46_16") (pintype "unspecified"))
    )
    (net (code "34") (name "Net-(U4-VCP)") (class "Default")
      (node (ref "C19") (pin "2") (pinfunction "2_2") (pintype "input"))
      (node (ref "U4") (pin "11") (pinfunction "VCP_11") (pintype "unspecified"))
    )
    (net (code "35") (name "Net-(U4-VINT)") (class "Default")
      (node (ref "C18") (pin "2") (pinfunction "2_2") (pintype "input"))
      (node (ref "U4") (pin "14") (pinfunction "VINT_14") (pintype "unspecified"))
    )
    (net (code "36") (name "Net-(U5-VCP)") (class "Default")
      (node (ref "C21") (pin "2") (pinfunction "2_2") (pintype "input"))
      (node (ref "U5") (pin "11") (pinfunction "VCP_11") (pintype "unspecified"))
    )
    (net (code "37") (name "Net-(U5-VINT)") (class "Default")
      (node (ref "C20") (pin "2") (pinfunction "2_2") (pintype "input"))
      (node (ref "U5") (pin "14") (pinfunction "VINT_14") (pintype "unspecified"))
    )
    (net (code "38") (name "Net-(U6-BOOTN)") (class "Default")
      (node (ref "R24") (pin "2") (pinfunction "2_2") (pintype "input"))
      (node (ref "TP7") (pin "1") (pinfunction "1_1") (pintype "unspecified"))
      (node (ref "U6") (pin "4") (pinfunction "BOOTN_4") (pintype "unspecified"))
    )
    (net (code "39") (name "Net-(U6-CAP)") (class "Default")
      (node (ref "C22") (pin "2") (pinfunction "2_2") (pintype "input"))
      (node (ref "U6") (pin "9") (pinfunction "CAP_9") (pintype "unspecified"))
    )
    (net (code "40") (name "Net-(U6-ENV_SCL)") (class "Default")
      (node (ref "R26") (pin "1") (pinfunction "1_1") (pintype "input"))
      (node (ref "U6") (pin "15") (pinfunction "ENV_SCL_15") (pintype "unspecified"))
    )
    (net (code "41") (name "Net-(U6-ENV_SDA)") (class "Default")
      (node (ref "R25") (pin "1") (pinfunction "1_1") (pintype "input"))
      (node (ref "U6") (pin "16") (pinfunction "ENV_SDA_16") (pintype "unspecified"))
    )
    (net (code "42") (name "Net-(U6-XIN32)") (class "Default")
      (node (ref "U6") (pin "27") (pinfunction "XIN32_27") (pintype "unspecified"))
      (node (ref "U7") (pin "3") (pinfunction "Out_3") (pintype "output"))
    )
    (net (code "43") (name "Net-(U8-TX)") (class "Default")
      (node (ref "U8") (pin "23") (pinfunction "TX_23") (pintype "input"))
      (node (ref "U9") (pin "2") (pinfunction "A_2") (pintype "unspecified"))
    )
    (net (code "44") (name "Net-(U8-XTAL1)") (class "Default")
      (node (ref "C23") (pin "1") (pinfunction "1_1") (pintype "input"))
      (node (ref "U8") (pin "2") (pinfunction "XTAL1_2") (pintype "input"))
      (node (ref "X1") (pin "2") (pinfunction "2_2") (pintype "unspecified"))
    )
    (net (code "45") (name "Net-(U8-XTAL2)") (class "Default")
      (node (ref "C24") (pin "1") (pinfunction "1_1") (pintype "input"))
      (node (ref "U8") (pin "3") (pinfunction "XTAL2_3") (pintype "input"))
      (node (ref "X1") (pin "1") (pinfunction "1_1") (pintype "unspecified"))
    )
    (net (code "46") (name "Net-(USBC1-CC1)") (class "Default")
      (node (ref "R2") (pin "2") (pinfunction "2_2") (pintype "input"))
      (node (ref "USBC1") (pin "A5") (pinfunction "CC1_A5") (pintype "unspecified"))
    )
    (net (code "47") (name "Net-(USBC1-CC2)") (class "Default")
      (node (ref "R3") (pin "2") (pinfunction "2_2") (pintype "input"))
      (node (ref "USBC1") (pin "B5") (pinfunction "CC2_B5") (pintype "unspecified"))
    )
    (net (code "48") (name "PA1") (class "Default")
      (node (ref "U2") (pin "4") (pinfunction "IO4_4") (pintype "unspecified"))
      (node (ref "U4") (pin "16") (pinfunction "AIN1_16") (pintype "unspecified"))
    )
    (net (code "49") (name "PA2") (class "Default")
      (node (ref "U2") (pin "5") (pinfunction "IO5_5") (pintype "unspecified"))
      (node (ref "U4") (pin "15") (pinfunction "AIN2_15") (pintype "unspecified"))
    )
    (net (code "50") (name "PB1") (class "Default")
      (node (ref "U2") (pin "6") (pinfunction "IO6_6") (pintype "unspecified"))
      (node (ref "U4") (pin "10") (pinfunction "BIN2_10") (pintype "unspecified"))
    )
    (net (code "51") (name "PB2") (class "Default")
      (node (ref "U2") (pin "7") (pinfunction "IO7_7") (pintype "unspecified"))
      (node (ref "U4") (pin "9") (pinfunction "BIN1_9") (pintype "unspecified"))
    )
    (net (code "52") (name "PC1") (class "Default")
      (node (ref "U2") (pin "23") (pinfunction "IO21_23") (pintype "unspecified"))
      (node (ref "U5") (pin "16") (pinfunction "AIN1_16") (pintype "unspecified"))
    )
    (net (code "53") (name "PC2") (class "Default")
      (node (ref "U2") (pin "18") (pinfunction "IO10_18") (pintype "unspecified"))
      (node (ref "U5") (pin "15") (pinfunction "AIN2_15") (pintype "unspecified"))
    )
    (net (code "54") (name "PD1") (class "Default")
      (node (ref "U2") (pin "25") (pinfunction "IO48_25") (pintype "unspecified"))
      (node (ref "U5") (pin "10") (pinfunction "BIN2_10") (pintype "unspecified"))
    )
    (net (code "55") (name "PD2") (class "Default")
      (node (ref "U2") (pin "24") (pinfunction "IO47_24") (pintype "unspecified"))
      (node (ref "U5") (pin "9") (pinfunction "BIN1_9") (pintype "unspecified"))
    )
    (net (code "56") (name "RTS") (class "Default")
      (node (ref "R1") (pin "1") (pinfunction "1_1") (pintype "input"))
      (node (ref "TP1") (pin "1") (pinfunction "1_1") (pintype "unspecified"))
    )
    (net (code "57") (name "SC16IS750_IRQ#") (class "Default")
      (node (ref "R27") (pin "2") (pinfunction "2_2") (pintype "input"))
      (node (ref "U2") (pin "17") (pinfunction "IO9_17") (pintype "unspecified"))
      (node (ref "U8") (pin "11") (pinfunction "IRQ#_11") (pintype "input"))
    )
    (net (code "58") (name "SCL") (class "Default")
      (node (ref "H2") (pin "1") (pinfunction "1_1") (pintype "unspecified"))
      (node (ref "U2") (pin "35") (pinfunction "IO42_35") (pintype "unspecified"))
      (node (ref "U6") (pin "19") (pinfunction "H_SCL/SCK/RX_19") (pintype "unspecified"))
      (node (ref "U8") (pin "9") (pinfunction "SCL_9") (pintype "input"))
    )
    (net (code "59") (name "SDA") (class "Default")
      (node (ref "H2") (pin "2") (pinfunction "2_2") (pintype "unspecified"))
      (node (ref "U2") (pin "12") (pinfunction "IO8_12") (pintype "unspecified"))
      (node (ref "U6") (pin "20") (pinfunction "H_SDA/H_MISO/TX_20") (pintype "unspecified"))
      (node (ref "U8") (pin "10") (pinfunction "SDA_10") (pintype "input"))
    )
    (net (code "60") (name "SD_CS") (class "Default")
      (node (ref "U2") (pin "31") (pinfunction "IO38_31") (pintype "unspecified"))
      (node (ref "U3") (pin "2") (pinfunction "2_2") (pintype "unspecified"))
    )
    (net (code "61") (name "SPI_SCK") (class "Default")
      (node (ref "U2") (pin "34") (pinfunction "IO41_34") (pintype "unspecified"))
      (node (ref "U3") (pin "5") (pinfunction "5_5") (pintype "unspecified"))
    )
    (net (code "62") (name "UART1_RX") (class "Default")
      (node (ref "H4") (pin "6") (pinfunction "6_6") (pintype "input"))
      (node (ref "R14") (pin "2") (pinfunction "2_2") (pintype "input"))
      (node (ref "U2") (pin "11") (pinfunction "IO18_11") (pintype "unspecified"))
    )
    (net (code "63") (name "UART1_TX") (class "Default")
      (node (ref "H4") (pin "5") (pinfunction "5_5") (pintype "input"))
      (node (ref "R13") (pin "2") (pinfunction "2_2") (pintype "input"))
      (node (ref "U2") (pin "10") (pinfunction "IO17_10") (pintype "unspecified"))
    )
    (net (code "64") (name "UART2_RX") (class "Default")
      (node (ref "H5") (pin "6") (pinfunction "6_6") (pintype "input"))
      (node (ref "R19") (pin "2") (pinfunction "2_2") (pintype "input"))
      (node (ref "U2") (pin "22") (pinfunction "IO14_22") (pintype "unspecified"))
      (node (ref "U8") (pin "24") (pinfunction "RX_24") (pintype "input"))
    )
    (net (code "65") (name "UART2_TX") (class "Default")
      (node (ref "H5") (pin "5") (pinfunction "5_5") (pintype "input"))
      (node (ref "R21") (pin "2") (pinfunction "2_2") (pintype "input"))
      (node (ref "U2") (pin "19") (pinfunction "IO11_19") (pintype "unspecified"))
      (node (ref "U9") (pin "4") (pinfunction "Y_4") (pintype "unspecified"))
    )
    (net (code "66") (name "UART2_TX_EN") (class "Default")
      (node (ref "R28") (pin "1") (pinfunction "1_1") (pintype "input"))
      (node (ref "U8") (pin "14") (pinfunction "GPIO2_14") (pintype "input"))
      (node (ref "U9") (pin "1") (pinfunction "OE_1") (pintype "unspecified"))
    )
    (net (code "67") (name "UART3_RX") (class "Default")
      (node (ref "H6") (pin "6") (pinfunction "6_6") (pintype "input"))
      (node (ref "R17") (pin "2") (pinfunction "2_2") (pintype "input"))
      (node (ref "U2") (pin "20") (pinfunction "IO12_20") (pintype "unspecified"))
    )
    (net (code "68") (name "UART3_TX") (class "Default")
      (node (ref "H6") (pin "5") (pinfunction "5_5") (pintype "input"))
      (node (ref "R18") (pin "2") (pinfunction "2_2") (pintype "input"))
      (node (ref "U2") (pin "21") (pinfunction "IO13_21") (pintype "unspecified"))
    )
    (net (code "69") (name "UART4_RX") (class "Default")
      (node (ref "H7") (pin "6") (pinfunction "6_6") (pintype "input"))
      (node (ref "R12") (pin "2") (pinfunction "2_2") (pintype "input"))
      (node (ref "U2") (pin "9") (pinfunction "IO16_9") (pintype "unspecified"))
    )
    (net (code "70") (name "UART4_TX") (class "Default")
      (node (ref "H7") (pin "5") (pinfunction "5_5") (pintype "input"))
      (node (ref "R11") (pin "2") (pinfunction "2_2") (pintype "input"))
      (node (ref "U2") (pin "8") (pinfunction "IO15_8") (pintype "unspecified"))
    )
    (net (code "71") (name "USB_D+") (class "Default")
      (node (ref "R9") (pin "1") (pinfunction "1_1") (pintype "input"))
      (node (ref "USBC1") (pin "A6") (pinfunction "DP1_A6") (pintype "unspecified"))
      (node (ref "USBC1") (pin "B6") (pinfunction "DP2_B6") (pintype "unspecified"))
    )
    (net (code "72") (name "USB_D-") (class "Default")
      (node (ref "R10") (pin "1") (pinfunction "1_1") (pintype "input"))
      (node (ref "USBC1") (pin "A7") (pinfunction "DN1_A7") (pintype "unspecified"))
      (node (ref "USBC1") (pin "B7") (pinfunction "DN2_B7") (pintype "unspecified"))
    )
    (net (code "73") (name "VBATT") (class "Default")
      (node (ref "H3") (pin "1") (pinfunction "1_1") (pintype "unspecified"))
      (node (ref "R22") (pin "2") (pinfunction "2_2") (pintype "input"))
    )
    (net (code "74") (name "VIN_") (class "Default")
      (node (ref "C10") (pin "1") (pinfunction "1_1") (pintype "input"))
      (node (ref "Q2") (pin "1") (pinfunction "G_1") (pintype "unspecified"))
      (node (ref "Q2") (pin "2") (pinfunction "S_2") (pintype "unspecified"))
      (node (ref "Q3") (pin "1") (pinfunction "G_1") (pintype "unspecified"))
      (node (ref "Q3") (pin "2") (pinfunction "S_2") (pintype "unspecified"))
      (node (ref "R5") (pin "1") (pinfunction "1_1") (pintype "input"))
      (node (ref "R6") (pin "2") (pinfunction "2_2") (pintype "input"))
      (node (ref "U1") (pin "2") (pinfunction "EN_2") (pintype "unspecified"))
      (node (ref "U1") (pin "3") (pinfunction "VIN_3") (pintype "unspecified"))
    )
    (net (code "75") (name "VIN_5V") (class "Default")
      (node (ref "H1") (pin "1") (pinfunction "1_1") (pintype "unspecified"))
      (node (ref "Q2") (pin "3") (pinfunction "D_3") (pintype "unspecified"))
      (node (ref "R5") (pin "2") (pinfunction "2_2") (pintype "input"))
      (node (ref "USBC1") (pin "A4B9") (pinfunction "VBUS_A4B9") (pintype "unspecified"))
      (node (ref "USBC1") (pin "B4A9") (pinfunction "VBUS_B4A9") (pintype "unspecified"))
    )
    (net (code "76") (name "unconnected-(U2-IO1-Pad39)") (class "Default")
      (node (ref "U2") (pin "39") (pinfunction "IO1_39") (pintype "unspecified+no_connect"))
    )
    (net (code "77") (name "unconnected-(U2-IO2-Pad38)") (class "Default")
      (node (ref "U2") (pin "38") (pinfunction "IO2_38") (pintype "unspecified+no_connect"))
    )
    (net (code "78") (name "unconnected-(U2-IO35-Pad28)") (class "Default")
      (node (ref "U2") (pin "28") (pinfunction "IO35_28") (pintype "unspecified+no_connect"))
    )
    (net (code "79") (name "unconnected-(U2-IO36-Pad29)") (class "Default")
      (node (ref "U2") (pin "29") (pinfunction "IO36_29") (pintype "unspecified+no_connect"))
    )
    (net (code "80") (name "unconnected-(U2-IO37-Pad30)") (class "Default")
      (node (ref "U2") (pin "30") (pinfunction "IO37_30") (pintype "unspecified+no_connect"))
    )
    (net (code "81") (name "unconnected-(U3-Pad1)") (class "Default")
      (node (ref "U3") (pin "1") (pinfunction "1_1") (pintype "unspecified+no_connect"))
    )
    (net (code "82") (name "unconnected-(U3-Pad8)") (class "Default")
      (node (ref "U3") (pin "8") (pinfunction "8_8") (pintype "unspecified+no_connect"))
    )
    (net (code "83") (name "unconnected-(U3-PadCD)") (class "Default")
      (node (ref "U3") (pin "CD") (pinfunction "CD_CD") (pintype "unspecified+no_connect"))
    )
    (net (code "84") (name "unconnected-(U6-H_CSN-Pad18)") (class "Default")
      (node (ref "U6") (pin "18") (pinfunction "H_CSN_18") (pintype "unspecified+no_connect"))
    )
    (net (code "85") (name "unconnected-(U6-RESV_NC-Pad1)") (class "Default")
      (node (ref "U6") (pin "1") (pinfunction "RESV_NC_1") (pintype "unspecified+no_connect"))
    )
    (net (code "86") (name "unconnected-(U6-RESV_NC-Pad7)") (class "Default")
      (node (ref "U6") (pin "7") (pinfunction "RESV_NC_7") (pintype "unspecified+no_connect"))
    )
    (net (code "87") (name "unconnected-(U6-RESV_NC-Pad8)") (class "Default")
      (node (ref "U6") (pin "8") (pinfunction "RESV_NC_8") (pintype "unspecified+no_connect"))
    )
    (net (code "88") (name "unconnected-(U6-RESV_NC-Pad12)") (class "Default")
      (node (ref "U6") (pin "12") (pinfunction "RESV_NC_12") (pintype "unspecified+no_connect"))
    )
    (net (code "89") (name "unconnected-(U6-RESV_NC-Pad13)") (class "Default")
      (node (ref "U6") (pin "13") (pinfunction "RESV_NC_13") (pintype "unspecified+no_connect"))
    )
    (net (code "90") (name "unconnected-(U6-RESV_NC-Pad21)") (class "Default")
      (node (ref "U6") (pin "21") (pinfunction "RESV_NC_21") (pintype "unspecified+no_connect"))
    )
    (net (code "91") (name "unconnected-(U6-RESV_NC-Pad22)") (class "Default")
      (node (ref "U6") (pin "22") (pinfunction "RESV_NC_22") (pintype "unspecified+no_connect"))
    )
    (net (code "92") (name "unconnected-(U6-RESV_NC-Pad23)") (class "Default")
      (node (ref "U6") (pin "23") (pinfunction "RESV_NC_23") (pintype "unspecified+no_connect"))
    )
    (net (code "93") (name "unconnected-(U6-RESV_NC-Pad24)") (class "Default")
      (node (ref "U6") (pin "24") (pinfunction "RESV_NC_24") (pintype "unspecified+no_connect"))
    )
    (net (code "94") (name "unconnected-(U8-CTS#-Pad22)") (class "Default")
      (node (ref "U8") (pin "22") (pinfunction "CTS#_22") (pintype "input+no_connect"))
    )
    (net (code "95") (name "unconnected-(U8-GPIO3-Pad15)") (class "Default")
      (node (ref "U8") (pin "15") (pinfunction "GPIO3_15") (pintype "input+no_connect"))
    )
    (net (code "96") (name "unconnected-(U8-GPIO5{slash}DTR#-Pad18)") (class "Default")
      (node (ref "U8") (pin "18") (pinfunction "GPIO5/DTR#_18") (pintype "input+no_connect"))
    )
    (net (code "97") (name "unconnected-(U8-GPIO6{slash}CD#-Pad19)") (class "Default")
      (node (ref "U8") (pin "19") (pinfunction "GPIO6/CD#_19") (pintype "input+no_connect"))
    )
    (net (code "98") (name "unconnected-(U8-GPIO7{slash}RI#-Pad20)") (class "Default")
      (node (ref "U8") (pin "20") (pinfunction "GPIO7/RI#_20") (pintype "input+no_connect"))
    )
    (net (code "99") (name "unconnected-(U8-RTS#-Pad21)") (class "Default")
      (node (ref "U8") (pin "21") (pinfunction "RTS#_21") (pintype "input+no_connect"))
    )
    (net (code "100") (name "unconnected-(U8-n.c.-Pad8)") (class "Default")
      (node (ref "U8") (pin "8") (pinfunction "n.c._8") (pintype "input+no_connect"))
    )
    (net (code "101") (name "unconnected-(USBC1-SBU1-PadA8)") (class "Default")
      (node (ref "USBC1") (pin "A8") (pinfunction "SBU1_A8") (pintype "unspecified+no_connect"))
    )
    (net (code "102") (name "unconnected-(USBC1-SBU2-PadB8)") (class "Default")
      (node (ref "USBC1") (pin "B8") (pinfunction "SBU2_B8") (pintype "unspecified+no_connect"))
    )
  )
)
